# avip-mod_v4_top.net
KiCad netlist of a schematic drawn in EAGLE
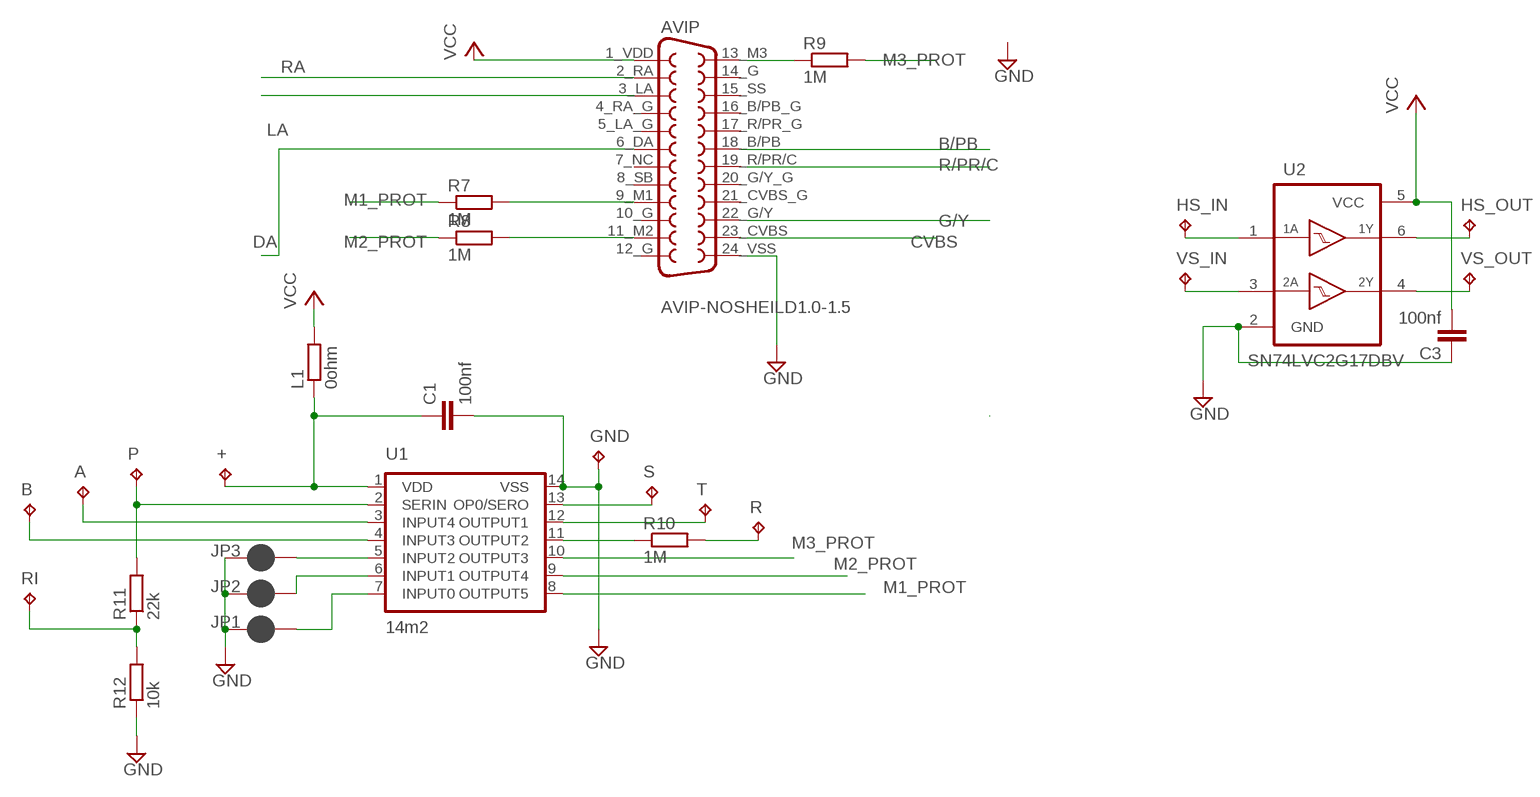
[diagram p0: schematic, sheet 1]

(export (version "E")
  (design (tool "Eeschema 10.0.6"))
  (components
    (comp (ref "+")
      (value "TPTP07SQ")
      (footprint "eagle-import:TP07SQ")
      (libsource (lib "eagle-import") (part "TPTP07SQ"))
    )
    (comp (ref "A")
      (value "TPTP07SQ")
      (footprint "eagle-import:TP07SQ")
      (libsource (lib "eagle-import") (part "TPTP07SQ"))
    )
    (comp (ref "AVIP")
      (value "AVIP-NOSHEILD1.0-1.5")
      (footprint "eagle-import:AVIP-1.0-1.5-NOSHEILD")
      (libsource (lib "eagle-import") (part "AVIP-NOSHEILD1.0-1.5"))
    )
    (comp (ref "B")
      (value "TPTP07SQ")
      (footprint "eagle-import:TP07SQ")
      (libsource (lib "eagle-import") (part "TPTP07SQ"))
    )
    (comp (ref "C1")
      (value "100nf")
      (footprint "eagle-import:C0603")
      (libsource (lib "eagle-import") (part "C-EUC0603"))
    )
    (comp (ref "C3")
      (value "100nf")
      (footprint "eagle-import:C0603")
      (libsource (lib "eagle-import") (part "C-EUC0603"))
    )
    (comp (ref "GND")
      (value "TPTP07SQ")
      (footprint "eagle-import:TP07SQ")
      (libsource (lib "eagle-import") (part "TPTP07SQ"))
    )
    (comp (ref "HS_IN")
      (value "TPTP07SQ")
      (footprint "eagle-import:TP07SQ")
      (libsource (lib "eagle-import") (part "TPTP07SQ"))
    )
    (comp (ref "HS_OUT")
      (value "TPTP07SQ")
      (footprint "eagle-import:TP07SQ")
      (libsource (lib "eagle-import") (part "TPTP07SQ"))
    )
    (comp (ref "JP1")
      (value "JUMPER-SMT_NO-SILK")
      (footprint "eagle-import:SMT-JUMPER")
      (libsource (lib "eagle-import") (part "JUMPER-SMT_NO-SILK"))
    )
    (comp (ref "JP2")
      (value "JUMPER-SMT_NO-SILK")
      (footprint "eagle-import:SMT-JUMPER")
      (libsource (lib "eagle-import") (part "JUMPER-SMT_NO-SILK"))
    )
    (comp (ref "JP3")
      (value "JUMPER-SMT_NO-SILK")
      (footprint "eagle-import:SMT-JUMPER")
      (libsource (lib "eagle-import") (part "JUMPER-SMT_NO-SILK"))
    )
    (comp (ref "L1")
      (value "0ohm")
      (footprint "eagle-import:R0603")
      (libsource (lib "eagle-import") (part "R-EU_R0603"))
    )
    (comp (ref "P")
      (value "TPTP07SQ")
      (footprint "eagle-import:TP07SQ")
      (libsource (lib "eagle-import") (part "TPTP07SQ"))
    )
    (comp (ref "R")
      (value "TPTP07SQ")
      (footprint "eagle-import:TP07SQ")
      (libsource (lib "eagle-import") (part "TPTP07SQ"))
    )
    (comp (ref "R7")
      (value "1M")
      (footprint "eagle-import:R0603")
      (libsource (lib "eagle-import") (part "R-EU_R0603"))
    )
    (comp (ref "R8")
      (value "1M")
      (footprint "eagle-import:R0603")
      (libsource (lib "eagle-import") (part "R-EU_R0603"))
    )
    (comp (ref "R9")
      (value "1M")
      (footprint "eagle-import:R0603")
      (libsource (lib "eagle-import") (part "R-EU_R0603"))
    )
    (comp (ref "R10")
      (value "1M")
      (footprint "eagle-import:R0603")
      (libsource (lib "eagle-import") (part "R-EU_R0603"))
    )
    (comp (ref "R11")
      (value "22k")
      (footprint "eagle-import:R0603")
      (libsource (lib "eagle-import") (part "R-EU_R0603"))
    )
    (comp (ref "R12")
      (value "10k")
      (footprint "eagle-import:R0603")
      (libsource (lib "eagle-import") (part "R-EU_R0603"))
    )
    (comp (ref "RI")
      (value "TPTP07SQ")
      (footprint "eagle-import:TP07SQ")
      (libsource (lib "eagle-import") (part "TPTP07SQ"))
    )
    (comp (ref "S")
      (value "TPTP07SQ")
      (footprint "eagle-import:TP07SQ")
      (libsource (lib "eagle-import") (part "TPTP07SQ"))
    )
    (comp (ref "T")
      (value "TPTP07SQ")
      (footprint "eagle-import:TP07SQ")
      (libsource (lib "eagle-import") (part "TPTP07SQ"))
    )
    (comp (ref "U1")
      (value "14m2")
      (footprint "eagle-import:SO14")
      (libsource (lib "eagle-import") (part "PICAXE-14AXE017M2SM"))
    )
    (comp (ref "U2")
      (value "SN74LVC2G17DBV")
      (footprint "eagle-import:SOT23-6")
      (libsource (lib "eagle-import") (part "SN74LVC2G17DBV"))
    )
    (comp (ref "VS_IN")
      (value "TPTP07SQ")
      (footprint "eagle-import:TP07SQ")
      (libsource (lib "eagle-import") (part "TPTP07SQ"))
    )
    (comp (ref "VS_OUT")
      (value "TPTP07SQ")
      (footprint "eagle-import:TP07SQ")
      (libsource (lib "eagle-import") (part "TPTP07SQ"))
    )
  )
  (nets
    (net (code "1") (name "/B{slash}PB") (class "Default")
      (node (ref "AVIP") (pin "18_B/PB") (pinfunction "18_B/PB_18_B/PB") (pintype "passive"))
    )
    (net (code "2") (name "/CVBS") (class "Default")
      (node (ref "AVIP") (pin "23_CVBS") (pinfunction "23_CVBS_23_CVBS") (pintype "passive"))
    )
    (net (code "3") (name "/DA") (class "Default")
      (node (ref "AVIP") (pin "6_DA") (pinfunction "6_DA_6_DA") (pintype "passive"))
    )
    (net (code "4") (name "/G{slash}Y") (class "Default")
      (node (ref "AVIP") (pin "22_G/Y") (pinfunction "22_G/Y_22_G/Y") (pintype "passive"))
    )
    (net (code "5") (name "/LA") (class "Default")
      (node (ref "AVIP") (pin "3_LA") (pinfunction "3_LA_3_LA") (pintype "passive"))
    )
    (net (code "6") (name "/M1_PROT") (class "Default")
      (node (ref "R7") (pin "1") (pinfunction "1_1") (pintype "passive"))
      (node (ref "U1") (pin "8") (pinfunction "OUTPUT5_8") (pintype "output"))
    )
    (net (code "7") (name "/M2_PROT") (class "Default")
      (node (ref "R8") (pin "1") (pinfunction "1_1") (pintype "passive"))
      (node (ref "U1") (pin "9") (pinfunction "OUTPUT4_9") (pintype "output"))
    )
    (net (code "8") (name "/M3_PROT") (class "Default")
      (node (ref "R9") (pin "2") (pinfunction "2_2") (pintype "passive"))
      (node (ref "U1") (pin "10") (pinfunction "OUTPUT3_10") (pintype "output"))
    )
    (net (code "9") (name "/RA") (class "Default")
      (node (ref "AVIP") (pin "2_RA") (pinfunction "2_RA_2_RA") (pintype "passive"))
    )
    (net (code "10") (name "/R{slash}PR{slash}C") (class "Default")
      (node (ref "AVIP") (pin "19_R/PR/C") (pinfunction "19_R/PR/C_19_R/PR/C") (pintype "passive"))
    )
    (net (code "11") (name "GND") (class "Default")
      (node (ref "AVIP") (pin "24_VSS") (pinfunction "25_VSS_24_VSS") (pintype "passive"))
      (node (ref "C1") (pin "2") (pinfunction "2_2") (pintype "passive"))
      (node (ref "C3") (pin "1") (pinfunction "1_1") (pintype "passive"))
      (node (ref "GND") (pin "TP") (pinfunction "TP_TP") (pintype "input"))
      (node (ref "JP1") (pin "1") (pinfunction "1_1") (pintype "passive"))
      (node (ref "JP2") (pin "1") (pinfunction "1_1") (pintype "passive"))
      (node (ref "JP3") (pin "1") (pinfunction "1_1") (pintype "passive"))
      (node (ref "R12") (pin "1") (pinfunction "1_1") (pintype "passive"))
      (node (ref "U1") (pin "14") (pinfunction "VSS_14") (pintype "power_in"))
      (node (ref "U2") (pin "2") (pinfunction "GND_2") (pintype "power_in"))
    )
    (net (code "12") (name "Net-(AVIP-Pad9_M1)") (class "Default")
      (node (ref "AVIP") (pin "9_M1") (pinfunction "9_M1_9_M1") (pintype "passive"))
      (node (ref "R7") (pin "2") (pinfunction "2_2") (pintype "passive"))
    )
    (net (code "13") (name "Net-(AVIP-Pad11_M2)") (class "Default")
      (node (ref "AVIP") (pin "11_M2") (pinfunction "11_M2_11_M2") (pintype "passive"))
      (node (ref "R8") (pin "2") (pinfunction "2_2") (pintype "passive"))
    )
    (net (code "14") (name "Net-(AVIP-Pad13_M3)") (class "Default")
      (node (ref "AVIP") (pin "13_M3") (pinfunction "13_M3_13_M3") (pintype "passive"))
      (node (ref "R9") (pin "1") (pinfunction "1_1") (pintype "passive"))
    )
    (net (code "15") (name "Net-(R-PadTP)") (class "Default")
      (node (ref "R") (pin "TP") (pinfunction "TP_TP") (pintype "input"))
      (node (ref "R10") (pin "2") (pinfunction "2_2") (pintype "passive"))
    )
    (net (code "16") (name "Net-(R11-Pad1)") (class "Default")
      (node (ref "R11") (pin "1") (pinfunction "1_1") (pintype "passive"))
      (node (ref "R12") (pin "2") (pinfunction "2_2") (pintype "passive"))
      (node (ref "RI") (pin "TP") (pinfunction "TP_TP") (pintype "input"))
    )
    (net (code "17") (name "Net-(U1-INPUT0)") (class "Default")
      (node (ref "JP1") (pin "2") (pinfunction "2_2") (pintype "passive"))
      (node (ref "U1") (pin "7") (pinfunction "INPUT0_7") (pintype "input"))
    )
    (net (code "18") (name "Net-(U1-INPUT1)") (class "Default")
      (node (ref "JP2") (pin "2") (pinfunction "2_2") (pintype "passive"))
      (node (ref "U1") (pin "6") (pinfunction "INPUT1_6") (pintype "input"))
    )
    (net (code "19") (name "Net-(U1-INPUT2)") (class "Default")
      (node (ref "JP3") (pin "2") (pinfunction "2_2") (pintype "passive"))
      (node (ref "U1") (pin "5") (pinfunction "INPUT2_5") (pintype "input"))
    )
    (net (code "20") (name "Net-(U1-INPUT3)") (class "Default")
      (node (ref "B") (pin "TP") (pinfunction "TP_TP") (pintype "input"))
      (node (ref "U1") (pin "4") (pinfunction "INPUT3_4") (pintype "input"))
    )
    (net (code "21") (name "Net-(U1-INPUT4)") (class "Default")
      (node (ref "A") (pin "TP") (pinfunction "TP_TP") (pintype "input"))
      (node (ref "U1") (pin "3") (pinfunction "INPUT4_3") (pintype "input"))
    )
    (net (code "22") (name "Net-(U1-OP0{slash}SERO)") (class "Default")
      (node (ref "S") (pin "TP") (pinfunction "TP_TP") (pintype "input"))
      (node (ref "U1") (pin "13") (pinfunction "OP0/SERO_13") (pintype "output"))
    )
    (net (code "23") (name "Net-(U1-OUTPUT1)") (class "Default")
      (node (ref "T") (pin "TP") (pinfunction "TP_TP") (pintype "input"))
      (node (ref "U1") (pin "12") (pinfunction "OUTPUT1_12") (pintype "output"))
    )
    (net (code "24") (name "Net-(U1-OUTPUT2)") (class "Default")
      (node (ref "R10") (pin "1") (pinfunction "1_1") (pintype "passive"))
      (node (ref "U1") (pin "11") (pinfunction "OUTPUT2_11") (pintype "output"))
    )
    (net (code "25") (name "Net-(U1-SERIN)") (class "Default")
      (node (ref "P") (pin "TP") (pinfunction "TP_TP") (pintype "input"))
      (node (ref "R11") (pin "2") (pinfunction "2_2") (pintype "passive"))
      (node (ref "U1") (pin "2") (pinfunction "SERIN_2") (pintype "input"))
    )
    (net (code "26") (name "Net-(U1-VDD)") (class "Default")
      (node (ref "+") (pin "TP") (pinfunction "TP_TP") (pintype "input"))
      (node (ref "C1") (pin "1") (pinfunction "1_1") (pintype "passive"))
      (node (ref "L1") (pin "1") (pinfunction "1_1") (pintype "passive"))
      (node (ref "U1") (pin "1") (pinfunction "VDD_1") (pintype "power_in"))
    )
    (net (code "27") (name "Net-(U2-1A)") (class "Default")
      (node (ref "HS_IN") (pin "TP") (pinfunction "TP_TP") (pintype "input"))
      (node (ref "U2") (pin "1") (pinfunction "1A_1") (pintype "input"))
    )
    (net (code "28") (name "Net-(U2-1Y)") (class "Default")
      (node (ref "HS_OUT") (pin "TP") (pinfunction "TP_TP") (pintype "input"))
      (node (ref "U2") (pin "6") (pinfunction "1Y_6") (pintype "output"))
    )
    (net (code "29") (name "Net-(U2-2A)") (class "Default")
      (node (ref "U2") (pin "3") (pinfunction "2A_3") (pintype "input"))
      (node (ref "VS_IN") (pin "TP") (pinfunction "TP_TP") (pintype "input"))
    )
    (net (code "30") (name "Net-(U2-2Y)") (class "Default")
      (node (ref "U2") (pin "4") (pinfunction "2Y_4") (pintype "output"))
      (node (ref "VS_OUT") (pin "TP") (pinfunction "TP_TP") (pintype "input"))
    )
    (net (code "31") (name "VCC") (class "Default")
      (node (ref "AVIP") (pin "1_VDD") (pinfunction "1_VDD_1_VDD") (pintype "power_in"))
      (node (ref "C3") (pin "2") (pinfunction "2_2") (pintype "passive"))
      (node (ref "L1") (pin "2") (pinfunction "2_2") (pintype "passive"))
      (node (ref "U2") (pin "5") (pinfunction "VCC_5") (pintype "power_in"))
    )
    (net (code "32") (name "unconnected-(AVIP-Pad4_RA_G)") (class "Default")
      (node (ref "AVIP") (pin "4_RA_G") (pinfunction "4_RA_G_4_RA_G") (pintype "passive"))
    )
    (net (code "33") (name "unconnected-(AVIP-Pad5_LA_G)") (class "Default")
      (node (ref "AVIP") (pin "5_LA_G") (pinfunction "5_LA_G_5_LA_G") (pintype "passive"))
    )
    (net (code "34") (name "unconnected-(AVIP-Pad7_NC)") (class "Default")
      (node (ref "AVIP") (pin "7_NC") (pinfunction "7_NC_7_NC") (pintype "passive"))
    )
    (net (code "35") (name "unconnected-(AVIP-Pad8_SB)") (class "Default")
      (node (ref "AVIP") (pin "8_SB") (pinfunction "8_SB_8_SB") (pintype "passive"))
    )
    (net (code "36") (name "unconnected-(AVIP-Pad10_G)") (class "Default")
      (node (ref "AVIP") (pin "10_G") (pinfunction "10_G_10_G") (pintype "passive"))
    )
    (net (code "37") (name "unconnected-(AVIP-Pad12_G)") (class "Default")
      (node (ref "AVIP") (pin "12_G") (pinfunction "12_G_12_G") (pintype "passive"))
    )
    (net (code "38") (name "unconnected-(AVIP-Pad14_G)") (class "Default")
      (node (ref "AVIP") (pin "14_G") (pinfunction "14_G_14_G") (pintype "passive"))
    )
    (net (code "39") (name "unconnected-(AVIP-Pad15_SS)") (class "Default")
      (node (ref "AVIP") (pin "15_SS") (pinfunction "15_SS_15_SS") (pintype "passive"))
    )
    (net (code "40") (name "unconnected-(AVIP-Pad16_B{slash}PB_G)") (class "Default")
      (node (ref "AVIP") (pin "16_B/PB_G") (pinfunction "16_B/PB_G_16_B/PB_G") (pintype "passive"))
    )
    (net (code "41") (name "unconnected-(AVIP-Pad17_R{slash}PR_G)") (class "Default")
      (node (ref "AVIP") (pin "17_R/PR_G") (pinfunction "17_R/PR_G_17_R/PR_G") (pintype "passive"))
    )
    (net (code "42") (name "unconnected-(AVIP-Pad20_G{slash}Y_G)") (class "Default")
      (node (ref "AVIP") (pin "20_G/Y_G") (pinfunction "20_G/Y_G_20_G/Y_G") (pintype "passive"))
    )
    (net (code "43") (name "unconnected-(AVIP-Pad21_CVBS_G)") (class "Default")
      (node (ref "AVIP") (pin "21_CVBS_G") (pinfunction "21_CVBS_G_21_CVBS_G") (pintype "passive"))
    )
  )
)
